# SCH_InfoBar-_ESP8266-12F__2024-08-24.net
KiCad netlist of a schematic drawn in EasyEDA
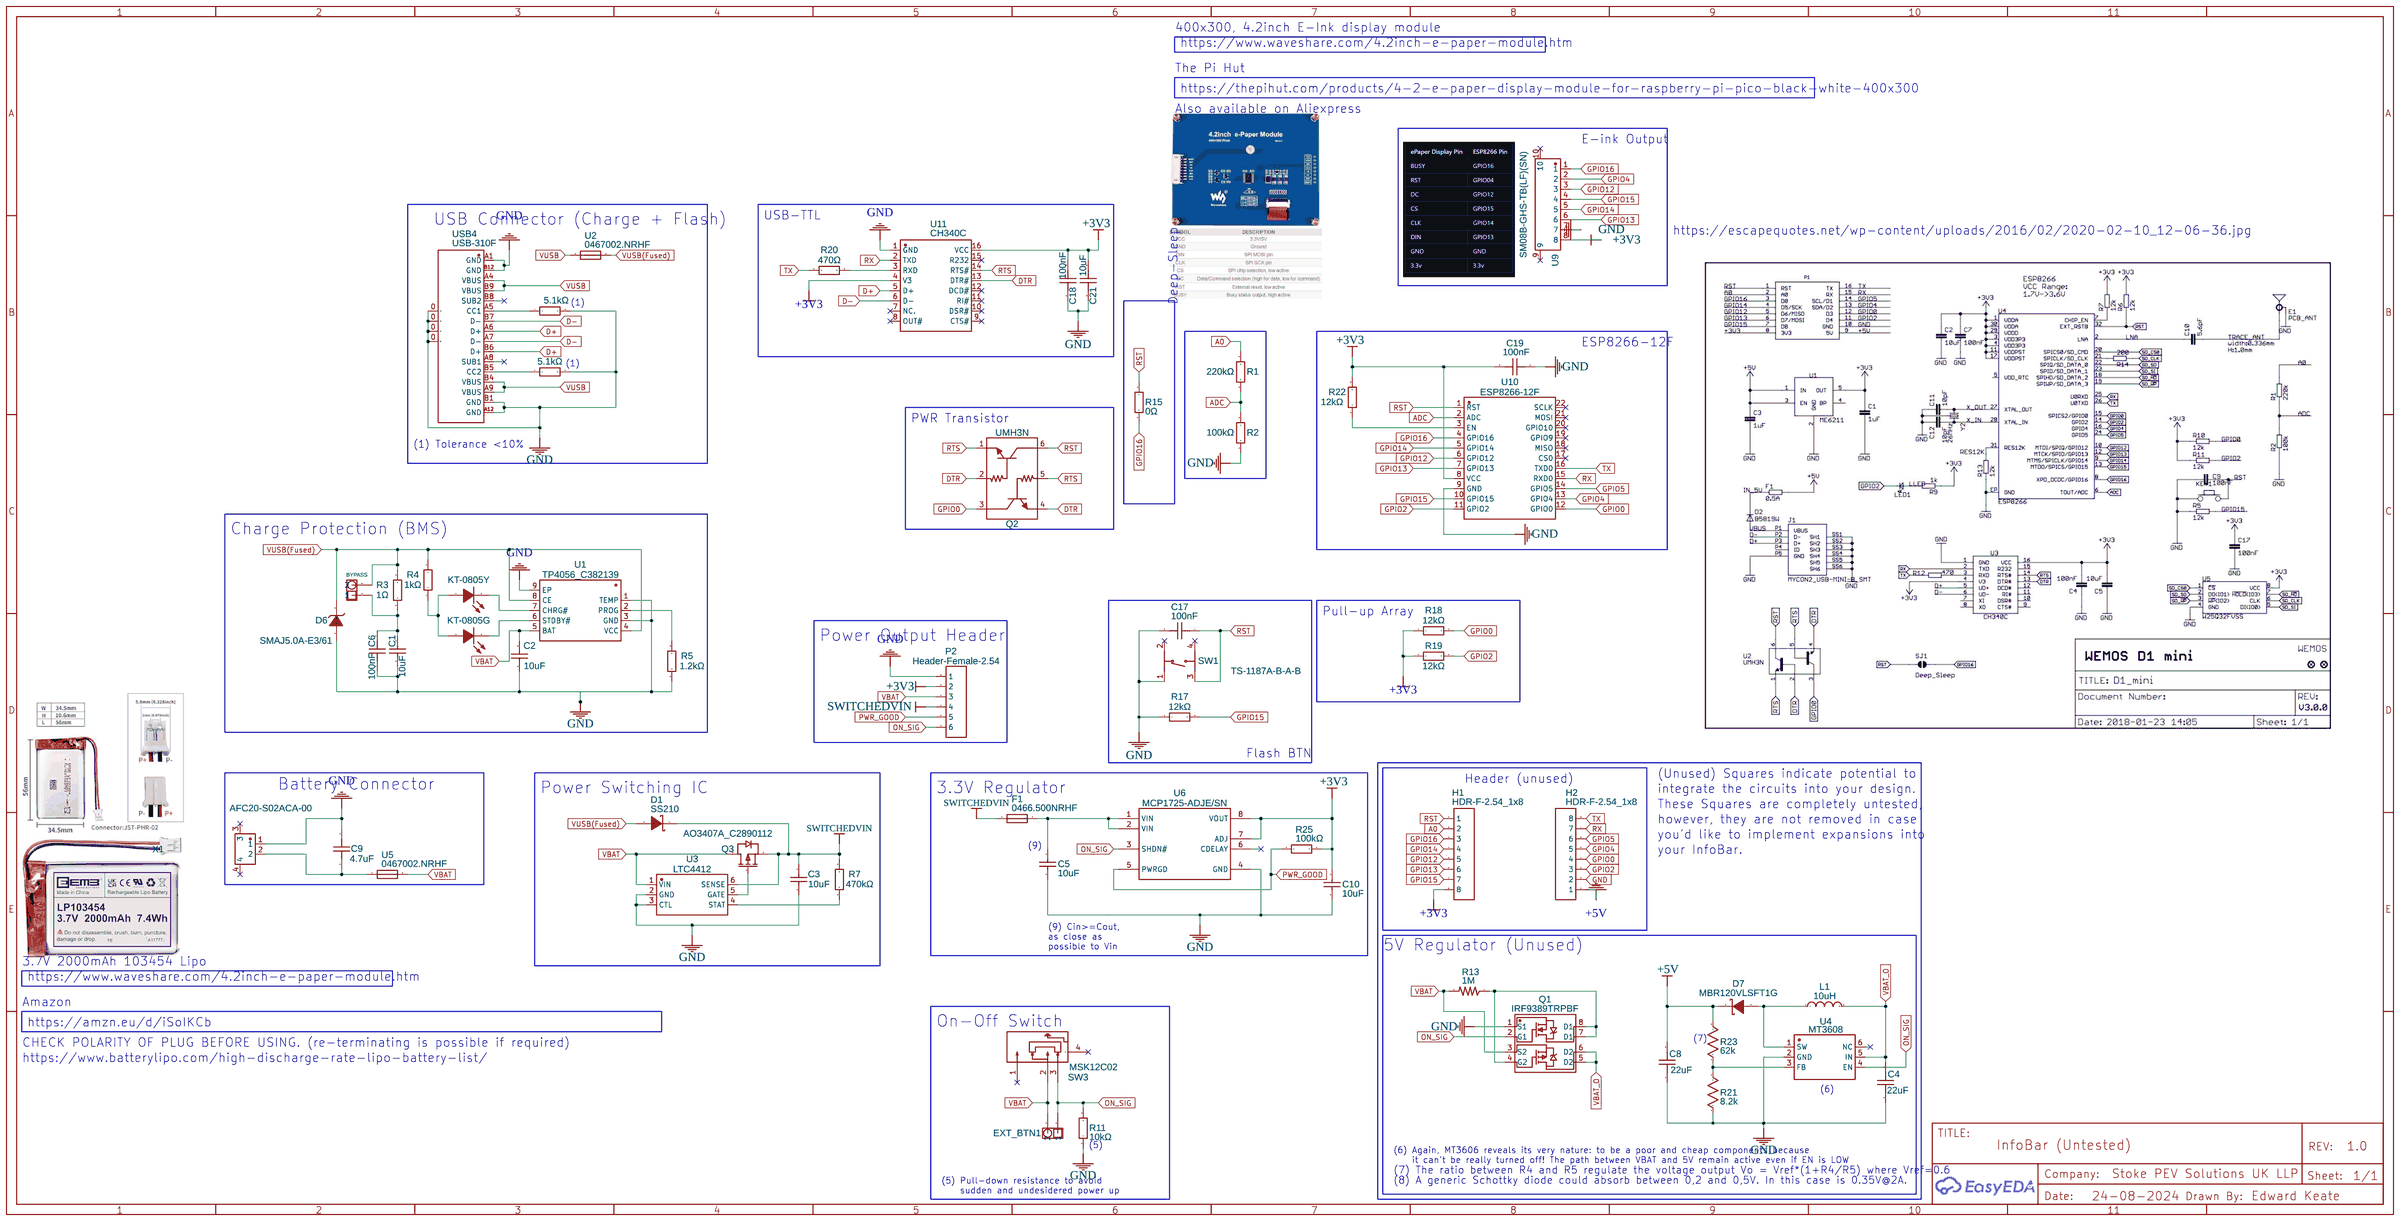
[diagram p0: schematic sheet]

(export (version "E")
  (design (tool "Eeschema 10.0.6"))
  (components
    (comp (ref "BYPASS")
      (value "Just a couple of 2.54-spaced pins")
      (fields (field (name "Manufacturer Part") "?"))
      (libsource (lib "") (part "Unknown_330_-615"))
    )
    (comp (ref "C1")
      (value "10uF")
      (fields
        (field (name "Manufacturer Part") "CL05A106MQ5NUNC")
        (field (name "Manufacturer") "SAMSUNG(三星)")
      )
      (libsource (lib "") (part "CL05A106MQ5NUNC"))
    )
    (comp (ref "C2")
      (value "10uF")
      (fields
        (field (name "Manufacturer Part") "CL05A106MQ5NUNC")
        (field (name "Manufacturer") "SAMSUNG(三星)")
      )
      (libsource (lib "") (part "CL05A106MQ5NUNC"))
    )
    (comp (ref "C3")
      (value "10uF")
      (fields
        (field (name "Manufacturer Part") "CL05A106MQ5NUNC")
        (field (name "Manufacturer") "SAMSUNG(三星)")
      )
      (libsource (lib "") (part "CL05A106MQ5NUNC"))
    )
    (comp (ref "C4")
      (value "22uF")
      (fields (field (name "Manufacturer Part") "?"))
      (libsource (lib "") (part "Cap_RAD-0.1_US"))
    )
    (comp (ref "C5")
      (value "10uF")
      (fields
        (field (name "Manufacturer Part") "CL05A106MQ5NUNC")
        (field (name "Manufacturer") "SAMSUNG(三星)")
      )
      (libsource (lib "") (part "CL05A106MQ5NUNC"))
    )
    (comp (ref "C6")
      (value "100nF")
      (fields
        (field (name "Manufacturer Part") "CC0603KRX7R9BB104")
        (field (name "Manufacturer") "YAGEO(国巨)")
      )
      (libsource (lib "") (part "CC0603KRX7R9BB104_1"))
    )
    (comp (ref "C8")
      (value "22uF")
      (fields (field (name "Manufacturer Part") "?"))
      (libsource (lib "") (part "Cap_RAD-0.1_US"))
    )
    (comp (ref "C9")
      (value "4.7uF")
      (fields (field (name "Manufacturer Part") "?"))
      (libsource (lib "") (part "Cap_RAD-0.1_US_1"))
    )
    (comp (ref "C10")
      (value "10uF")
      (fields
        (field (name "Manufacturer Part") "CL05A106MQ5NUNC")
        (field (name "Manufacturer") "SAMSUNG(三星)")
      )
      (libsource (lib "") (part "CL05A106MQ5NUNC"))
    )
    (comp (ref "C17")
      (value "100nF")
      (fields
        (field (name "Manufacturer Part") "CC0603KRX7R9BB104")
        (field (name "Manufacturer") "YAGEO(国巨)")
      )
      (libsource (lib "") (part "CC0603KRX7R9BB104"))
    )
    (comp (ref "C18")
      (value "100nF")
      (fields
        (field (name "Manufacturer Part") "CC0603KRX7R9BB104")
        (field (name "Manufacturer") "YAGEO(国巨)")
      )
      (libsource (lib "") (part "CC0603KRX7R9BB104_2"))
    )
    (comp (ref "C19")
      (value "100nF")
      (fields
        (field (name "Manufacturer Part") "CC0603KRX7R9BB104")
        (field (name "Manufacturer") "YAGEO(国巨)")
      )
      (libsource (lib "") (part "CC0603KRX7R9BB104"))
    )
    (comp (ref "C21")
      (value "10uF")
      (fields
        (field (name "Manufacturer Part") "CL10A106KP8NNNC")
        (field (name "Manufacturer") "SAMSUNG(三星)")
      )
      (libsource (lib "") (part "CL10A106KP8NNNC"))
    )
    (comp (ref "D1")
      (value "SS210")
      (fields (field (name "Manufacturer") "MDD(辰达半导体)"))
      (libsource (lib "") (part "SS210"))
    )
    (comp (ref "D6")
      (value "SMAJ5.0A-E3/61")
      (fields (field (name "Manufacturer") "VISHAY(威世)"))
      (libsource (lib "") (part "SMAJ5.0A-E3/61"))
    )
    (comp (ref "D7")
      (value "MBR120VLSFT1G")
      (fields (field (name "Manufacturer") "ON Semicon"))
      (libsource (lib "") (part "MBR120VLSFT1G"))
    )
    (comp (ref "EXT_BTN1")
      (value "Just a couple of 2.54-spaced pins")
      (fields (field (name "Manufacturer Part") "?"))
      (libsource (lib "") (part "Unknown_1030_-70"))
    )
    (comp (ref "F1")
      (value "0466.500NRHF")
      (fields (field (name "Manufacturer") "Littelfuse(美国力特)"))
      (libsource (lib "") (part "0466.500NRHF"))
    )
    (comp (ref "H1") (value "HDR-F-2.54_1x8") (libsource (lib "") (part "HDR-F-2.54_1x8")))
    (comp (ref "H2") (value "HDR-F-2.54_1x8") (libsource (lib "") (part "HDR-F-2.54_1x8_1")))
    (comp (ref "L1")
      (value "10uH")
      (fields
        (field (name "Manufacturer Part") "LQH5BPN100M38L")
        (field (name "Manufacturer") "Murata Electronics")
      )
      (libsource (lib "") (part "LQH5BPN100M38L"))
    )
    (comp (ref "LED2")
      (value "KT-0805G")
      (fields (field (name "Manufacturer") "KENTO"))
      (libsource (lib "") (part "0805G (Green)"))
    )
    (comp (ref "LED3")
      (value "KT-0805Y")
      (fields (field (name "Manufacturer Part") "KT-0805黄灯") (field (name "Manufacturer") "KENTO"))
      (libsource (lib "") (part "17-21SUYC/TR8"))
    )
    (comp (ref "P2")
      (value "Header-Female-2.54")
      (fields (field (name "Manufacturer Part") "Female header 1*6p") (field (name "Manufacturer") "BOOMELE"))
      (libsource (lib "") (part "Unknown_930_-505"))
    )
    (comp (ref "Q1")
      (value "IRF9389TRPBF")
      (fields (field (name "Manufacturer") "Infineon"))
      (libsource (lib "") (part "IRF9389TRPBF detailed"))
    )
    (comp (ref "Q2")
      (value "UMH3N")
      (fields (field (name "Manufacturer") "CJ(江苏长电/长晶)"))
      (libsource (lib "") (part "UMH3N"))
    )
    (comp (ref "Q3")
      (value "AO3407A_C2890112")
      (fields (field (name "Manufacturer Part") "AO3407A") (field (name "Manufacturer") "TECH PUBLIC(台舟)"))
      (libsource (lib "") (part "AO3407A_C2890112"))
    )
    (comp (ref "R1")
      (value "220kΩ")
      (fields
        (field (name "Manufacturer Part") "0603WAF2203T5E")
        (field (name "Manufacturer") "UNI-ROYAL(厚声)")
      )
      (libsource (lib "") (part "0603WAF2203T5E"))
    )
    (comp (ref "R2")
      (value "100kΩ")
      (fields
        (field (name "Manufacturer Part") "0603WAF1003T5E")
        (field (name "Manufacturer") "UNI-ROYAL(厚声)")
      )
      (libsource (lib "") (part "0603WAF1003T5E"))
    )
    (comp (ref "R3")
      (value "1Ω")
      (fields
        (field (name "Manufacturer Part") "0805W8F100KT5E")
        (field (name "Manufacturer") "UNI-ROYAL(厚声)")
      )
      (libsource (lib "") (part "0805W8F100KT5E"))
    )
    (comp (ref "R4")
      (value "1kΩ")
      (fields
        (field (name "Manufacturer Part") "0603WAF1001T5E")
        (field (name "Manufacturer") "UNI-ROYAL(厚声)")
      )
      (libsource (lib "") (part "0603WAF1001T5E"))
    )
    (comp (ref "R5")
      (value "1.2kΩ")
      (fields
        (field (name "Manufacturer Part") "0603WAF1201T5E")
        (field (name "Manufacturer") "UNI-ROYAL(厚声)")
      )
      (libsource (lib "") (part "0603WAF1201T5E"))
    )
    (comp (ref "R7")
      (value "470kΩ")
      (fields
        (field (name "Manufacturer Part") "0603WAF4703T5E")
        (field (name "Manufacturer") "UNI-ROYAL(厚声)")
      )
      (libsource (lib "") (part "0603WAF4703T5E"))
    )
    (comp (ref "R10")
      (value "5.1kΩ")
      (fields
        (field (name "Manufacturer Part") "0402WGF5101TCE")
        (field (name "Manufacturer") "UNI-ROYAL(厚声)")
      )
      (libsource (lib "") (part "0402WGF5101TCE"))
    )
    (comp (ref "R11")
      (value "10kΩ")
      (fields
        (field (name "Manufacturer Part") "0603WAF1002T5E")
        (field (name "Manufacturer") "UNI-ROYAL(厚声)")
      )
      (libsource (lib "") (part "0603WAF1002T5E"))
    )
    (comp (ref "R13") (value "1M") (libsource (lib "") (part "Unknown_1440_-220")))
    (comp (ref "R15")
      (value "0Ω")
      (fields
        (field (name "Manufacturer Part") "0603WAF0000T5E")
        (field (name "Manufacturer") "UNI-ROYAL(厚声)")
      )
      (libsource (lib "") (part "0603WAF0000T5E"))
    )
    (comp (ref "R17")
      (value "12kΩ")
      (fields
        (field (name "Manufacturer Part") "0603WAF1202T5E")
        (field (name "Manufacturer") "UNI-ROYAL(厚声)")
      )
      (libsource (lib "") (part "0603WAF1202T5E"))
    )
    (comp (ref "R18")
      (value "12kΩ")
      (fields
        (field (name "Manufacturer Part") "0603WAF1202T5E")
        (field (name "Manufacturer") "UNI-ROYAL(厚声)")
      )
      (libsource (lib "") (part "0603WAF1202T5E"))
    )
    (comp (ref "R19")
      (value "12kΩ")
      (fields
        (field (name "Manufacturer Part") "0603WAF1202T5E")
        (field (name "Manufacturer") "UNI-ROYAL(厚声)")
      )
      (libsource (lib "") (part "0603WAF1202T5E"))
    )
    (comp (ref "R20")
      (value "470Ω")
      (fields
        (field (name "Manufacturer Part") "0603WAF4700T5E")
        (field (name "Manufacturer") "UNI-ROYAL(厚声)")
      )
      (libsource (lib "") (part "0603WAF4700T5E"))
    )
    (comp (ref "R21")
      (value "8.2k")
      (fields (field (name "Manufacturer Part") "?"))
      (libsource (lib "") (part "Res_AXIAL-0.3(1/8W)_US"))
    )
    (comp (ref "R22")
      (value "12kΩ")
      (fields
        (field (name "Manufacturer Part") "0603WAF1202T5E")
        (field (name "Manufacturer") "UNI-ROYAL(厚声)")
      )
      (libsource (lib "") (part "0603WAF1202T5E_1"))
    )
    (comp (ref "R23")
      (value "62k")
      (fields (field (name "Manufacturer Part") "?"))
      (libsource (lib "") (part "Res_AXIAL-0.3(1/8W)_US"))
    )
    (comp (ref "R25")
      (value "100kΩ")
      (fields
        (field (name "Manufacturer Part") "0603WAF1003T5E")
        (field (name "Manufacturer") "UNI-ROYAL(厚声)")
      )
      (libsource (lib "") (part "0603WAF1003T5E_1"))
    )
    (comp (ref "R26")
      (value "5.1kΩ")
      (fields
        (field (name "Manufacturer Part") "0402WGF5101TCE")
        (field (name "Manufacturer") "UNI-ROYAL(厚声)")
      )
      (libsource (lib "") (part "0402WGF5101TCE"))
    )
    (comp (ref "SW1")
      (value "TS-1187A-B-A-B")
      (fields (field (name "Manufacturer") "XKB Connectivity(中国星坤)"))
      (libsource (lib "") (part "TS-1187A-B-A-B"))
    )
    (comp (ref "SW3")
      (value "MSK12C02")
      (fields (field (name "Manufacturer") "SHOU HAN(首韩)"))
      (libsource (lib "") (part "MSK12C02"))
    )
    (comp (ref "U1")
      (value "TP4056_C382139")
      (fields (field (name "Manufacturer Part") "TP4056") (field (name "Manufacturer") "TPOWER(天源)"))
      (libsource (lib "") (part "TP4056_C382139"))
    )
    (comp (ref "U2")
      (value "0467002.NRHF")
      (fields (field (name "Manufacturer") "Littelfuse(美国力特)"))
      (libsource (lib "") (part "0467002.NRHF"))
    )
    (comp (ref "U3")
      (value "LTC4412")
      (fields (field (name "Manufacturer Part") "LTC4412IS6#TRPBF") (field (name "Manufacturer") "ADI(亚德诺)"))
      (libsource (lib "") (part "LTC4412IS6#TRPBF_C521306"))
    )
    (comp (ref "U4")
      (value "MT3608")
      (fields (field (name "Manufacturer") "AEROSEMI"))
      (libsource (lib "") (part "MT3608"))
    )
    (comp (ref "U5")
      (value "0467002.NRHF")
      (fields (field (name "Manufacturer") "Littelfuse(美国力特)"))
      (libsource (lib "") (part "0467002.NRHF"))
    )
    (comp (ref "U6")
      (value "MCP1725-ADJE/SN")
      (fields (field (name "Manufacturer") "MICROCHIP(美国微芯)"))
      (libsource (lib "") (part "MCP1725-ADJE/SN"))
    )
    (comp (ref "U9")
      (value "SM08B-GHS-TB(LF)(SN)")
      (fields (field (name "Manufacturer") "JST"))
      (libsource (lib "") (part "SM08B-GHS-TB(LF)(SN)"))
    )
    (comp (ref "U10")
      (value "ESP8266-12F")
      (fields
        (field (name "Manufacturer Part") "ESP-12F(ESP8266MOD)")
        (field (name "Manufacturer") "Ai-Thinker(安信可)")
      )
      (libsource (lib "") (part "ESP-12F(ESP8266MOD)"))
    )
    (comp (ref "U11")
      (value "CH340C")
      (fields (field (name "Manufacturer") "WCH(南京沁恒)"))
      (libsource (lib "") (part "CH340C"))
    )
    (comp (ref "USB4")
      (value "USB-310F")
      (fields (field (name "Manufacturer Part") "USB-310F-B-SU") (field (name "Manufacturer") "HOOYA(皓宇电子)"))
      (libsource (lib "") (part "USB-310F"))
    )
    (comp (ref "X1")
      (value "AFC20-S02ACA-00")
      (fields (field (name "Manufacturer") "JS(钜硕电子)"))
      (libsource (lib "") (part "AFC20-S02ACA-00"))
    )
  )
  (nets
    (net (code "1") (name "+3V3") (class "Default")
      (node (ref "C10") (pin "1") (pinfunction "1_1") (pintype "input"))
      (node (ref "C18") (pin "2") (pinfunction "2_2") (pintype "unspecified"))
      (node (ref "C19") (pin "2") (pinfunction "2_2") (pintype "unspecified"))
      (node (ref "C21") (pin "1") (pinfunction "1_1") (pintype "unspecified"))
      (node (ref "H1") (pin "8") (pinfunction "8_8") (pintype "unspecified"))
      (node (ref "P2") (pin "2") (pinfunction "2_2") (pintype "input"))
      (node (ref "R18") (pin "1") (pinfunction "1_1") (pintype "input"))
      (node (ref "R19") (pin "1") (pinfunction "1_1") (pintype "input"))
      (node (ref "R22") (pin "2") (pinfunction "2_2") (pintype "input"))
      (node (ref "R25") (pin "2") (pinfunction "2_2") (pintype "input"))
      (node (ref "U10") (pin "8") (pinfunction "VCC_8") (pintype "unspecified"))
      (node (ref "U11") (pin "16") (pinfunction "VCC_16") (pintype "unspecified"))
      (node (ref "U11") (pin "4") (pinfunction "V3_4") (pintype "unspecified"))
      (node (ref "U6") (pin "7") (pinfunction "ADJ_7") (pintype "unspecified"))
      (node (ref "U6") (pin "8") (pinfunction "VOUT_8") (pintype "passive"))
      (node (ref "U9") (pin "8") (pinfunction "8_8") (pintype "unspecified"))
    )
    (net (code "2") (name "+5V") (class "Default")
      (node (ref "C8") (pin "2") (pinfunction "2_2") (pintype "unspecified"))
      (node (ref "D7") (pin "1") (pinfunction "K_1") (pintype "unspecified"))
      (node (ref "H2") (pin "1") (pinfunction "1_1") (pintype "unspecified"))
      (node (ref "R23") (pin "2") (pinfunction "2_2") (pintype "unspecified"))
    )
    (net (code "3") (name "A0") (class "Default")
      (node (ref "H1") (pin "2") (pinfunction "2_2") (pintype "unspecified"))
      (node (ref "R1") (pin "1") (pinfunction "1_1") (pintype "input"))
    )
    (net (code "4") (name "ADC") (class "Default")
      (node (ref "R1") (pin "2") (pinfunction "2_2") (pintype "input"))
      (node (ref "R2") (pin "1") (pinfunction "1_1") (pintype "input"))
      (node (ref "U10") (pin "2") (pinfunction "ADC_2") (pintype "unspecified"))
    )
    (net (code "5") (name "D+") (class "Default")
      (node (ref "U11") (pin "5") (pinfunction "D+_5") (pintype "unspecified"))
      (node (ref "USB4") (pin "A6") (pinfunction "D+_A6") (pintype "unspecified"))
      (node (ref "USB4") (pin "B6") (pinfunction "D+_B6") (pintype "unspecified"))
    )
    (net (code "6") (name "D-") (class "Default")
      (node (ref "U11") (pin "6") (pinfunction "D-_6") (pintype "unspecified"))
      (node (ref "USB4") (pin "A7") (pinfunction "D-_A7") (pintype "unspecified"))
      (node (ref "USB4") (pin "B7") (pinfunction "D-_B7") (pintype "unspecified"))
    )
    (net (code "7") (name "DTR") (class "Default")
      (node (ref "Q2") (pin "2") (pinfunction "B_2") (pintype "unspecified"))
      (node (ref "Q2") (pin "4") (pinfunction "E_4") (pintype "unspecified"))
      (node (ref "U11") (pin "13") (pinfunction "DTR#_13") (pintype "unspecified"))
    )
    (net (code "8") (name "GND") (class "Default")
      (node (ref "C1") (pin "2") (pinfunction "2_2") (pintype "input"))
      (node (ref "C10") (pin "2") (pinfunction "2_2") (pintype "input"))
      (node (ref "C17") (pin "2") (pinfunction "2_2") (pintype "unspecified"))
      (node (ref "C18") (pin "1") (pinfunction "1_1") (pintype "unspecified"))
      (node (ref "C19") (pin "1") (pinfunction "1_1") (pintype "unspecified"))
      (node (ref "C2") (pin "2") (pinfunction "2_2") (pintype "input"))
      (node (ref "C21") (pin "2") (pinfunction "2_2") (pintype "unspecified"))
      (node (ref "C3") (pin "2") (pinfunction "2_2") (pintype "input"))
      (node (ref "C4") (pin "1") (pinfunction "1_1") (pintype "unspecified"))
      (node (ref "C5") (pin "2") (pinfunction "2_2") (pintype "input"))
      (node (ref "C6") (pin "2") (pinfunction "2_2") (pintype "unspecified"))
      (node (ref "C8") (pin "1") (pinfunction "1_1") (pintype "unspecified"))
      (node (ref "C9") (pin "1") (pinfunction "1_1") (pintype "unspecified"))
      (node (ref "D6") (pin "2") (pinfunction "A_2") (pintype "unspecified"))
      (node (ref "H2") (pin "2") (pinfunction "2_2") (pintype "unspecified"))
      (node (ref "P2") (pin "1") (pinfunction "1_1") (pintype "input"))
      (node (ref "Q1") (pin "1") (pinfunction "S1_1") (pintype "unspecified"))
      (node (ref "R10") (pin "2") (pinfunction "2_2") (pintype "input"))
      (node (ref "R11") (pin "1") (pinfunction "1_1") (pintype "input"))
      (node (ref "R17") (pin "1") (pinfunction "1_1") (pintype "input"))
      (node (ref "R2") (pin "2") (pinfunction "2_2") (pintype "input"))
      (node (ref "R21") (pin "1") (pinfunction "1_1") (pintype "unspecified"))
      (node (ref "R26") (pin "2") (pinfunction "2_2") (pintype "input"))
      (node (ref "R5") (pin "2") (pinfunction "2_2") (pintype "input"))
      (node (ref "SW1") (pin "1") (pinfunction "A_1") (pintype "unspecified"))
      (node (ref "U1") (pin "1") (pinfunction "TEMP_1") (pintype "unspecified"))
      (node (ref "U1") (pin "3") (pinfunction "GND_3") (pintype "unspecified"))
      (node (ref "U1") (pin "9") (pinfunction "EP_9") (pintype "unspecified"))
      (node (ref "U10") (pin "9") (pinfunction "GND_9") (pintype "unspecified"))
      (node (ref "U11") (pin "1") (pinfunction "GND_1") (pintype "unspecified"))
      (node (ref "U3") (pin "2") (pinfunction "GND_2") (pintype "unspecified"))
      (node (ref "U3") (pin "3") (pinfunction "CTL_3") (pintype "unspecified"))
      (node (ref "U4") (pin "2") (pinfunction "GND_2") (pintype "unspecified"))
      (node (ref "U6") (pin "4") (pinfunction "GND_4") (pintype "passive"))
      (node (ref "U9") (pin "7") (pinfunction "7_7") (pintype "unspecified"))
      (node (ref "USB4") (pin "0") (pinfunction "0_0") (pintype "unspecified"))
      (node (ref "USB4") (pin "A1") (pinfunction "GND_A1") (pintype "unspecified"))
      (node (ref "USB4") (pin "A12") (pinfunction "GND_A12") (pintype "unspecified"))
      (node (ref "USB4") (pin "B1") (pinfunction "GND_B1") (pintype "unspecified"))
      (node (ref "USB4") (pin "B12") (pinfunction "GND_B12") (pintype "unspecified"))
      (node (ref "X1") (pin "1") (pinfunction "1_1") (pintype "unspecified"))
    )
    (net (code "9") (name "GPIO0") (class "Default")
      (node (ref "H2") (pin "4") (pinfunction "4_4") (pintype "unspecified"))
      (node (ref "Q2") (pin "3") (pinfunction "C_3") (pintype "unspecified"))
      (node (ref "R18") (pin "2") (pinfunction "2_2") (pintype "input"))
      (node (ref "U10") (pin "12") (pinfunction "GPIO0_12") (pintype "unspecified"))
    )
    (net (code "10") (name "GPIO2") (class "Default")
      (node (ref "H2") (pin "3") (pinfunction "3_3") (pintype "unspecified"))
      (node (ref "R19") (pin "2") (pinfunction "2_2") (pintype "input"))
      (node (ref "U10") (pin "11") (pinfunction "GPIO2_11") (pintype "unspecified"))
    )
    (net (code "11") (name "GPIO4") (class "Default")
      (node (ref "H2") (pin "5") (pinfunction "5_5") (pintype "unspecified"))
      (node (ref "U10") (pin "13") (pinfunction "GPIO4_13") (pintype "unspecified"))
      (node (ref "U9") (pin "2") (pinfunction "2_2") (pintype "unspecified"))
    )
    (net (code "12") (name "GPIO5") (class "Default")
      (node (ref "H2") (pin "6") (pinfunction "6_6") (pintype "unspecified"))
      (node (ref "U10") (pin "14") (pinfunction "GPIO5_14") (pintype "unspecified"))
    )
    (net (code "13") (name "GPIO12") (class "Default")
      (node (ref "H1") (pin "5") (pinfunction "5_5") (pintype "unspecified"))
      (node (ref "U10") (pin "6") (pinfunction "GPIO12_6") (pintype "unspecified"))
      (node (ref "U9") (pin "3") (pinfunction "3_3") (pintype "unspecified"))
    )
    (net (code "14") (name "GPIO13") (class "Default")
      (node (ref "H1") (pin "6") (pinfunction "6_6") (pintype "unspecified"))
      (node (ref "U10") (pin "7") (pinfunction "GPIO13_7") (pintype "unspecified"))
      (node (ref "U9") (pin "6") (pinfunction "6_6") (pintype "unspecified"))
    )
    (net (code "15") (name "GPIO14") (class "Default")
      (node (ref "H1") (pin "4") (pinfunction "4_4") (pintype "unspecified"))
      (node (ref "U10") (pin "5") (pinfunction "GPIO14_5") (pintype "unspecified"))
      (node (ref "U9") (pin "5") (pinfunction "5_5") (pintype "unspecified"))
    )
    (net (code "16") (name "GPIO15") (class "Default")
      (node (ref "H1") (pin "7") (pinfunction "7_7") (pintype "unspecified"))
      (node (ref "R17") (pin "2") (pinfunction "2_2") (pintype "input"))
      (node (ref "U10") (pin "10") (pinfunction "GPIO15_10") (pintype "unspecified"))
      (node (ref "U9") (pin "4") (pinfunction "4_4") (pintype "unspecified"))
    )
    (net (code "17") (name "GPIO16") (class "Default")
      (node (ref "H1") (pin "3") (pinfunction "3_3") (pintype "unspecified"))
      (node (ref "R15") (pin "2") (pinfunction "2_2") (pintype "input"))
      (node (ref "U10") (pin "4") (pinfunction "GPIO16_4") (pintype "unspecified"))
      (node (ref "U9") (pin "1") (pinfunction "1_1") (pintype "unspecified"))
    )
    (net (code "18") (name "Net-(BYPASS-Pad1)") (class "Default")
      (node (ref "BYPASS") (pin "1") (pinfunction "1_1") (pintype "unspecified"))
      (node (ref "C1") (pin "1") (pinfunction "1_1") (pintype "input"))
      (node (ref "C6") (pin "1") (pinfunction "1_1") (pintype "unspecified"))
      (node (ref "R3") (pin "2") (pinfunction "2_2") (pintype "input"))
    )
    (net (code "19") (name "Net-(C5-Pad1)") (class "Default")
      (node (ref "C5") (pin "1") (pinfunction "1_1") (pintype "input"))
      (node (ref "F1") (pin "2") (pinfunction "2_2") (pintype "unspecified"))
      (node (ref "U6") (pin "1") (pinfunction "VIN_1") (pintype "passive"))
      (node (ref "U6") (pin "2") (pinfunction "VIN_2") (pintype "passive"))
    )
    (net (code "20") (name "Net-(C9-Pad2)") (class "Default")
      (node (ref "C9") (pin "2") (pinfunction "2_2") (pintype "unspecified"))
      (node (ref "U5") (pin "1") (pinfunction "1_1") (pintype "unspecified"))
      (node (ref "X1") (pin "2") (pinfunction "2_2") (pintype "unspecified"))
    )
    (net (code "21") (name "Net-(D7-A)") (class "Default")
      (node (ref "D7") (pin "2") (pinfunction "A_2") (pintype "unspecified"))
      (node (ref "L1") (pin "1") (pinfunction "1_1") (pintype "unspecified"))
      (node (ref "U4") (pin "1") (pinfunction "SW_1") (pintype "unspecified"))
    )
    (net (code "22") (name "Net-(LED2-A)") (class "Default")
      (node (ref "LED2") (pin "1") (pinfunction "A_1") (pintype "unspecified"))
      (node (ref "LED3") (pin "1") (pinfunction "+_1") (pintype "unspecified"))
      (node (ref "R4") (pin "1") (pinfunction "1_1") (pintype "input"))
    )
    (net (code "23") (name "Net-(LED2-K)") (class "Default")
      (node (ref "LED2") (pin "2") (pinfunction "K_2") (pintype "unspecified"))
      (node (ref "U1") (pin "6") (pinfunction "STDBY#_6") (pintype "unspecified"))
    )
    (net (code "24") (name "Net-(LED3--)") (class "Default")
      (node (ref "LED3") (pin "2") (pinfunction "-_2") (pintype "unspecified"))
      (node (ref "U1") (pin "7") (pinfunction "CHRG#_7") (pintype "unspecified"))
    )
    (net (code "25") (name "Net-(Q1-G2)") (class "Default")
      (node (ref "Q1") (pin "4") (pinfunction "G2_4") (pintype "unspecified"))
      (node (ref "Q1") (pin "7") (pinfunction "D1_7") (pintype "unspecified"))
      (node (ref "Q1") (pin "8") (pinfunction "D1_8") (pintype "unspecified"))
      (node (ref "R13") (pin "1") (pinfunction "1_1") (pintype "unspecified"))
    )
    (net (code "26") (name "Net-(Q3-G)") (class "Default")
      (node (ref "Q3") (pin "1") (pinfunction "G_1") (pintype "unspecified"))
      (node (ref "U3") (pin "5") (pinfunction "GATE_5") (pintype "unspecified"))
    )
    (net (code "27") (name "Net-(U1-PROG)") (class "Default")
      (node (ref "R5") (pin "1") (pinfunction "1_1") (pintype "input"))
      (node (ref "U1") (pin "2") (pinfunction "PROG_2") (pintype "unspecified"))
    )
    (net (code "28") (name "Net-(U3-STAT)") (class "Default")
      (node (ref "R7") (pin "1") (pinfunction "1_1") (pintype "input"))
      (node (ref "U3") (pin "4") (pinfunction "STAT_4") (pintype "unspecified"))
    )
    (net (code "29") (name "Net-(U4-FB)") (class "Default")
      (node (ref "R21") (pin "2") (pinfunction "2_2") (pintype "unspecified"))
      (node (ref "R23") (pin "1") (pinfunction "1_1") (pintype "unspecified"))
      (node (ref "U4") (pin "3") (pinfunction "FB_3") (pintype "unspecified"))
    )
    (net (code "30") (name "Net-(U10-EN)") (class "Default")
      (node (ref "R22") (pin "1") (pinfunction "1_1") (pintype "input"))
      (node (ref "U10") (pin "3") (pinfunction "EN_3") (pintype "unspecified"))
    )
    (net (code "31") (name "Net-(U11-RXD)") (class "Default")
      (node (ref "R20") (pin "2") (pinfunction "2_2") (pintype "input"))
      (node (ref "U11") (pin "3") (pinfunction "RXD_3") (pintype "unspecified"))
    )
    (net (code "32") (name "Net-(USB4-CC1)") (class "Default")
      (node (ref "R26") (pin "1") (pinfunction "1_1") (pintype "input"))
      (node (ref "USB4") (pin "A5") (pinfunction "CC1_A5") (pintype "unspecified"))
    )
    (net (code "33") (name "Net-(USB4-CC2)") (class "Default")
      (node (ref "R10") (pin "1") (pinfunction "1_1") (pintype "input"))
      (node (ref "USB4") (pin "B5") (pinfunction "CC2_B5") (pintype "unspecified"))
    )
    (net (code "34") (name "ON_SIG") (class "Default")
      (node (ref "EXT_BTN1") (pin "1") (pinfunction "1_1") (pintype "unspecified"))
      (node (ref "P2") (pin "6") (pinfunction "6_6") (pintype "input"))
      (node (ref "Q1") (pin "2") (pinfunction "G1_2") (pintype "unspecified"))
      (node (ref "R11") (pin "2") (pinfunction "2_2") (pintype "input"))
      (node (ref "SW3") (pin "3") (pinfunction "3_3") (pintype "unspecified"))
      (node (ref "U4") (pin "4") (pinfunction "EN_4") (pintype "unspecified"))
      (node (ref "U6") (pin "3") (pinfunction "SHDN#_3") (pintype "unspecified"))
    )
    (net (code "35") (name "PWR_GOOD") (class "Default")
      (node (ref "P2") (pin "5") (pinfunction "5_5") (pintype "input"))
      (node (ref "R25") (pin "1") (pinfunction "1_1") (pintype "input"))
      (node (ref "U6") (pin "5") (pinfunction "PWRGD_5") (pintype "passive"))
    )
    (net (code "36") (name "RST") (class "Default")
      (node (ref "C17") (pin "1") (pinfunction "1_1") (pintype "unspecified"))
      (node (ref "H1") (pin "1") (pinfunction "1_1") (pintype "unspecified"))
      (node (ref "Q2") (pin "6") (pinfunction "C_6") (pintype "unspecified"))
      (node (ref "R15") (pin "1") (pinfunction "1_1") (pintype "input"))
      (node (ref "SW1") (pin "3") (pinfunction "C_3") (pintype "unspecified"))
      (node (ref "U10") (pin "1") (pinfunction "RST_1") (pintype "unspecified"))
    )
    (net (code "37") (name "RTS") (class "Default")
      (node (ref "Q2") (pin "1") (pinfunction "E_1") (pintype "unspecified"))
      (node (ref "Q2") (pin "5") (pinfunction "B_5") (pintype "unspecified"))
      (node (ref "U11") (pin "14") (pinfunction "RTS#_14") (pintype "unspecified"))
    )
    (net (code "38") (name "RX") (class "Default")
      (node (ref "H2") (pin "7") (pinfunction "7_7") (pintype "unspecified"))
      (node (ref "U10") (pin "15") (pinfunction "RXD0_15") (pintype "unspecified"))
      (node (ref "U11") (pin "2") (pinfunction "TXD_2") (pintype "unspecified"))
    )
    (net (code "39") (name "SWITCHEDVIN") (class "Default")
      (node (ref "C3") (pin "1") (pinfunction "1_1") (pintype "input"))
      (node (ref "D1") (pin "1") (pinfunction "K_1") (pintype "unspecified"))
      (node (ref "F1") (pin "1") (pinfunction "1_1") (pintype "unspecified"))
      (node (ref "P2") (pin "4") (pinfunction "4_4") (pintype "input"))
      (node (ref "Q3") (pin "2") (pinfunction "S_2") (pintype "unspecified"))
      (node (ref "R7") (pin "2") (pinfunction "2_2") (pintype "input"))
      (node (ref "U3") (pin "6") (pinfunction "SENSE_6") (pintype "unspecified"))
    )
    (net (code "40") (name "TX") (class "Default")
      (node (ref "H2") (pin "8") (pinfunction "8_8") (pintype "unspecified"))
      (node (ref "R20") (pin "1") (pinfunction "1_1") (pintype "input"))
      (node (ref "U10") (pin "16") (pinfunction "TXD0_16") (pintype "unspecified"))
    )
    (net (code "41") (name "VBAT") (class "Default")
      (node (ref "C2") (pin "1") (pinfunction "1_1") (pintype "input"))
      (node (ref "EXT_BTN1") (pin "2") (pinfunction "2_2") (pintype "unspecified"))
      (node (ref "P2") (pin "3") (pinfunction "3_3") (pintype "input"))
      (node (ref "Q1") (pin "3") (pinfunction "S2_3") (pintype "unspecified"))
      (node (ref "Q3") (pin "3") (pinfunction "D_3") (pintype "unspecified"))
      (node (ref "R13") (pin "2") (pinfunction "2_2") (pintype "unspecified"))
      (node (ref "SW3") (pin "2") (pinfunction "2_2") (pintype "unspecified"))
      (node (ref "U1") (pin "5") (pinfunction "BAT_5") (pintype "unspecified"))
      (node (ref "U3") (pin "1") (pinfunction "VIN_1") (pintype "unspecified"))
      (node (ref "U5") (pin "2") (pinfunction "2_2") (pintype "unspecified"))
    )
    (net (code "42") (name "VBAT_O") (class "Default")
      (node (ref "C4") (pin "2") (pinfunction "2_2") (pintype "unspecified"))
      (node (ref "L1") (pin "2") (pinfunction "2_2") (pintype "unspecified"))
      (node (ref "Q1") (pin "5") (pinfunction "D2_5") (pintype "unspecified"))
      (node (ref "Q1") (pin "6") (pinfunction "D2_6") (pintype "unspecified"))
      (node (ref "U4") (pin "5") (pinfunction "IN_5") (pintype "unspecified"))
    )
    (net (code "43") (name "VUSB") (class "Default")
      (node (ref "U2") (pin "1") (pinfunction "1_1") (pintype "unspecified"))
      (node (ref "USB4") (pin "A4") (pinfunction "VBUS_A4") (pintype "unspecified"))
      (node (ref "USB4") (pin "A9") (pinfunction "VBUS_A9") (pintype "unspecified"))
      (node (ref "USB4") (pin "B4") (pinfunction "VBUS_B4") (pintype "unspecified"))
      (node (ref "USB4") (pin "B9") (pinfunction "VBUS_B9") (pintype "unspecified"))
    )
    (net (code "44") (name "VUSB(Fused)") (class "Default")
      (node (ref "BYPASS") (pin "2") (pinfunction "2_2") (pintype "unspecified"))
      (node (ref "D1") (pin "2") (pinfunction "A_2") (pintype "unspecified"))
      (node (ref "D6") (pin "1") (pinfunction "C_1") (pintype "unspecified"))
      (node (ref "R3") (pin "1") (pinfunction "1_1") (pintype "input"))
      (node (ref "R4") (pin "2") (pinfunction "2_2") (pintype "input"))
      (node (ref "U1") (pin "4") (pinfunction "VCC_4") (pintype "unspecified"))
      (node (ref "U1") (pin "8") (pinfunction "CE_8") (pintype "unspecified"))
      (node (ref "U2") (pin "2") (pinfunction "2_2") (pintype "unspecified"))
    )
    (net (code "45") (name "unconnected-(SW1-B-Pad2)") (class "Default")
      (node (ref "SW1") (pin "2") (pinfunction "B_2") (pintype "unspecified+no_connect"))
    )
    (net (code "46") (name "unconnected-(SW1-D-Pad4)") (class "Default")
      (node (ref "SW1") (pin "4") (pinfunction "D_4") (pintype "unspecified+no_connect"))
    )
    (net (code "47") (name "unconnected-(SW3-Pad1)") (class "Default")
      (node (ref "SW3") (pin "1") (pinfunction "1_1") (pintype "unspecified+no_connect"))
    )
    (net (code "48") (name "unconnected-(SW3-Pad4)") (class "Default")
      (node (ref "SW3") (pin "4") (pinfunction "4_4") (pintype "unspecified+no_connect"))
    )
    (net (code "49") (name "unconnected-(U4-NC-Pad6)") (class "Default")
      (node (ref "U4") (pin "6") (pinfunction "NC_6") (pintype "unspecified+no_connect"))
    )
    (net (code "50") (name "unconnected-(U6-CDELAY-Pad6)") (class "Default")
      (node (ref "U6") (pin "6") (pinfunction "CDELAY_6") (pintype "unspecified+no_connect"))
    )
    (net (code "51") (name "unconnected-(U9-Pad9)") (class "Default")
      (node (ref "U9") (pin "9") (pinfunction "9_9") (pintype "unspecified+no_connect"))
    )
    (net (code "52") (name "unconnected-(U9-Pad10)") (class "Default")
      (node (ref "U9") (pin "10") (pinfunction "10_10") (pintype "unspecified+no_connect"))
    )
    (net (code "53") (name "unconnected-(U10-CS0-Pad17)") (class "Default")
      (node (ref "U10") (pin "17") (pinfunction "CS0_17") (pintype "unspecified+no_connect"))
    )
    (net (code "54") (name "unconnected-(U10-GPIO9-Pad19)") (class "Default")
      (node (ref "U10") (pin "19") (pinfunction "GPIO9_19") (pintype "unspecified+no_connect"))
    )
    (net (code "55") (name "unconnected-(U10-GPIO10-Pad20)") (class "Default")
      (node (ref "U10") (pin "20") (pinfunction "GPIO10_20") (pintype "unspecified+no_connect"))
    )
    (net (code "56") (name "unconnected-(U10-MISO-Pad18)") (class "Default")
      (node (ref "U10") (pin "18") (pinfunction "MISO_18") (pintype "unspecified+no_connect"))
    )
    (net (code "57") (name "unconnected-(U10-MOSI-Pad21)") (class "Default")
      (node (ref "U10") (pin "21") (pinfunction "MOSI_21") (pintype "unspecified+no_connect"))
    )
    (net (code "58") (name "unconnected-(U10-SCLK-Pad22)") (class "Default")
      (node (ref "U10") (pin "22") (pinfunction "SCLK_22") (pintype "unspecified+no_connect"))
    )
    (net (code "59") (name "unconnected-(U11-CTS#-Pad9)") (class "Default")
      (node (ref "U11") (pin "9") (pinfunction "CTS#_9") (pintype "unspecified+no_connect"))
    )
    (net (code "60") (name "unconnected-(U11-DCD#-Pad12)") (class "Default")
      (node (ref "U11") (pin "12") (pinfunction "DCD#_12") (pintype "unspecified+no_connect"))
    )
    (net (code "61") (name "unconnected-(U11-DSR#-Pad10)") (class "Default")
      (node (ref "U11") (pin "10") (pinfunction "DSR#_10") (pintype "unspecified+no_connect"))
    )
    (net (code "62") (name "unconnected-(U11-NC.-Pad7)") (class "Default")
      (node (ref "U11") (pin "7") (pinfunction "NC._7") (pintype "unspecified+no_connect"))
    )
    (net (code "63") (name "unconnected-(U11-OUT#-Pad8)") (class "Default")
      (node (ref "U11") (pin "8") (pinfunction "OUT#_8") (pintype "unspecified+no_connect"))
    )
    (net (code "64") (name "unconnected-(U11-R232-Pad15)") (class "Default")
      (node (ref "U11") (pin "15") (pinfunction "R232_15") (pintype "unspecified+no_connect"))
    )
    (net (code "65") (name "unconnected-(U11-RI#-Pad11)") (class "Default")
      (node (ref "U11") (pin "11") (pinfunction "RI#_11") (pintype "unspecified+no_connect"))
    )
    (net (code "66") (name "unconnected-(USB4-SUB1-PadA8)") (class "Default")
      (node (ref "USB4") (pin "A8") (pinfunction "SUB1_A8") (pintype "unspecified+no_connect"))
    )
    (net (code "67") (name "unconnected-(USB4-SUB2-PadB8)") (class "Default")
      (node (ref "USB4") (pin "B8") (pinfunction "SUB2_B8") (pintype "unspecified+no_connect"))
    )
    (net (code "68") (name "unconnected-(X1-Pad3)") (class "Default")
      (node (ref "X1") (pin "3") (pinfunction "3_3") (pintype "unspecified+no_connect"))
    )
    (net (code "69") (name "unconnected-(X1-Pad4)") (class "Default")
      (node (ref "X1") (pin "4") (pinfunction "4_4") (pintype "unspecified+no_connect"))
    )
  )
)
